# 7_segment.net
KiCad netlist of a schematic drawn in Altium Designer
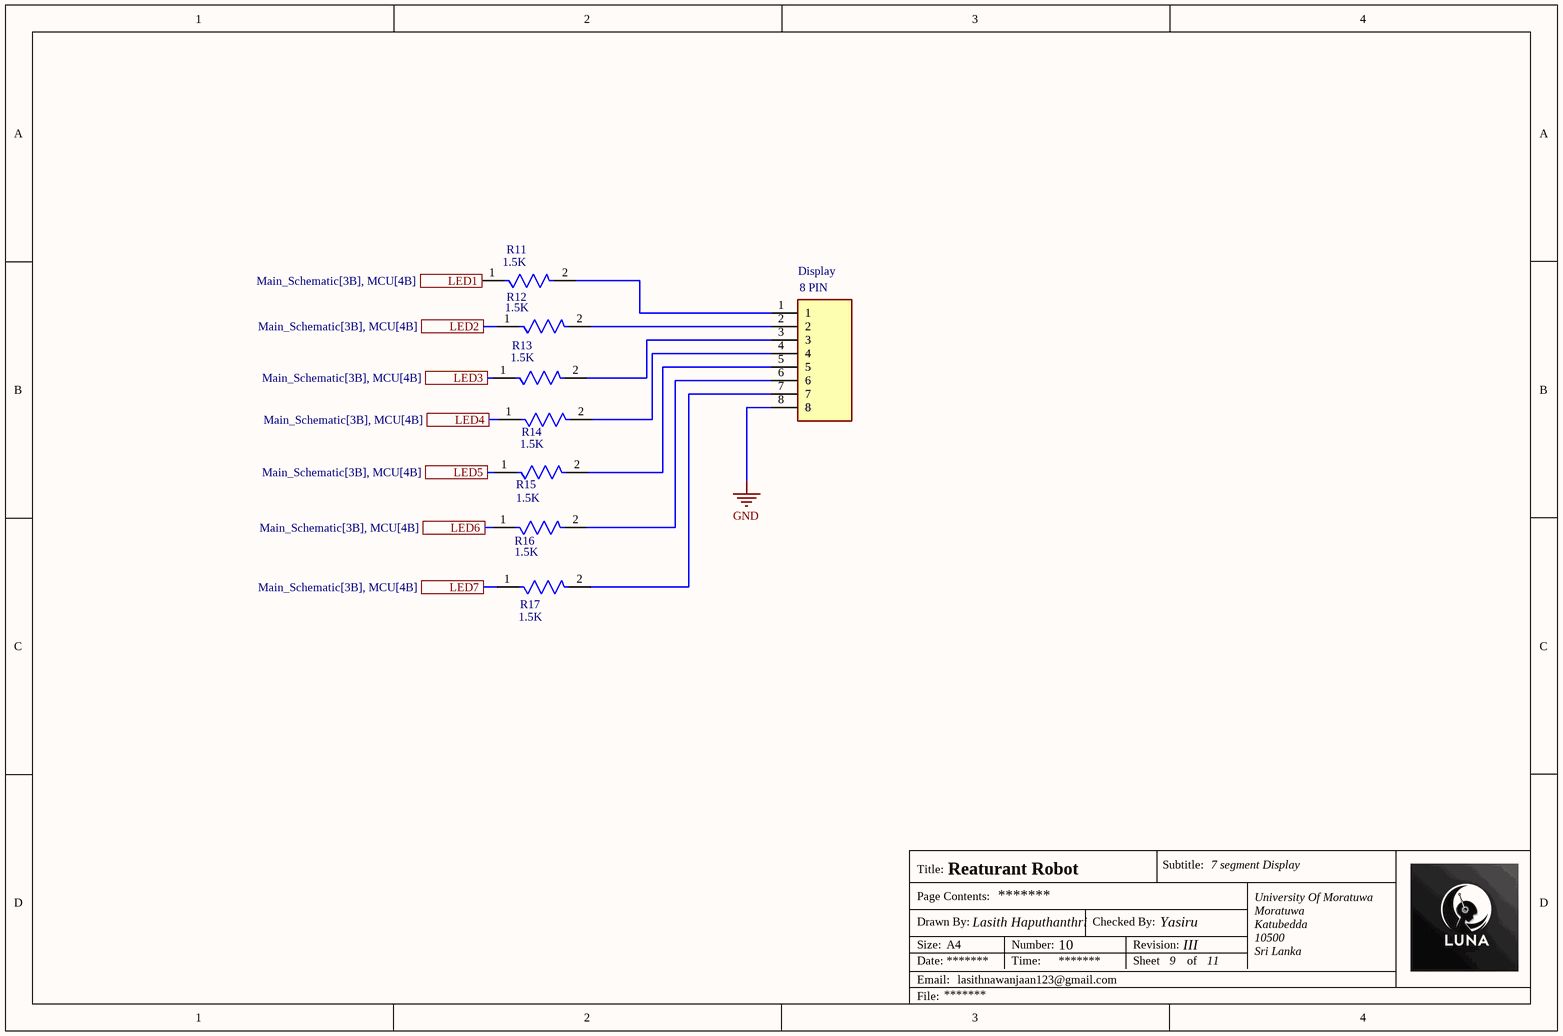
[diagram p0: 7 segment.SchDoc]

(export (version "E")
  (design (tool "Eeschema 10.0.6"))
  (components
    (comp (ref "Display")
      (value "8 PIN")
      (footprint "SamacSys:SHDR8W60P0X250_1X8_2250X640X880P")
      (description "Connector")
      (fields (field (name "MANUFACTURER_PART_NUMBER") "B08B-XASK-1 (LF)(SN)"))
      (libsource (lib "*") (part "B08B-XASK-1__LF__SN_"))
    )
    (comp (ref "R11")
      (value "1.5K")
      (footprint "FP-AF0603-IPC_B")
      (description "Anti-Sulfurated Chip Resistors Automotive Grade 1.5kΩ 1% 100ppm/°C 0603")
      (fields (field (name "TOLERANCE") "1%"))
      (libsource (lib "Altium Content Vault") (part "1029c3af85768c4190bb7ad29bc67b5"))
    )
    (comp (ref "R12")
      (value "1.5K")
      (footprint "FP-AF0603-IPC_B")
      (description "Anti-Sulfurated Chip Resistors Automotive Grade 1.5kΩ 1% 100ppm/°C 0603")
      (fields (field (name "TOLERANCE") "1%"))
      (libsource (lib "Altium Content Vault") (part "1029c3af85768c4190bb7ad29bc67b5"))
    )
    (comp (ref "R13")
      (value "1.5K")
      (footprint "FP-AF0603-IPC_B")
      (description "Anti-Sulfurated Chip Resistors Automotive Grade 1.5kΩ 1% 100ppm/°C 0603")
      (fields (field (name "TOLERANCE") "1%"))
      (libsource (lib "Altium Content Vault") (part "1029c3af85768c4190bb7ad29bc67b5"))
    )
    (comp (ref "R14")
      (value "1.5K")
      (footprint "FP-AF0603-IPC_B")
      (description "Anti-Sulfurated Chip Resistors Automotive Grade 1.5kΩ 1% 100ppm/°C 0603")
      (fields (field (name "TOLERANCE") "1%"))
      (libsource (lib "Altium Content Vault") (part "1029c3af85768c4190bb7ad29bc67b5"))
    )
    (comp (ref "R15")
      (value "1.5K")
      (footprint "FP-AF0603-IPC_B")
      (description "Anti-Sulfurated Chip Resistors Automotive Grade 1.5kΩ 1% 100ppm/°C 0603")
      (fields (field (name "TOLERANCE") "1%"))
      (libsource (lib "Altium Content Vault") (part "1029c3af85768c4190bb7ad29bc67b5"))
    )
    (comp (ref "R16")
      (value "1.5K")
      (footprint "FP-AF0603-IPC_B")
      (description "Anti-Sulfurated Chip Resistors Automotive Grade 1.5kΩ 1% 100ppm/°C 0603")
      (fields (field (name "TOLERANCE") "1%"))
      (libsource (lib "Altium Content Vault") (part "1029c3af85768c4190bb7ad29bc67b5"))
    )
    (comp (ref "R17")
      (value "1.5K")
      (footprint "FP-AF0603-IPC_B")
      (description "Anti-Sulfurated Chip Resistors Automotive Grade 1.5kΩ 1% 100ppm/°C 0603")
      (fields (field (name "TOLERANCE") "1%"))
      (libsource (lib "Altium Content Vault") (part "1029c3af85768c4190bb7ad29bc67b5"))
    )
  )
  (nets
    (net (code "1") (name "/LED1") (class "Default")
      (node (ref "R11") (pin "1") (pinfunction "1_1") (pintype "passive"))
    )
    (net (code "2") (name "/LED2") (class "Default")
      (node (ref "R12") (pin "1") (pinfunction "1_1") (pintype "passive"))
    )
    (net (code "3") (name "/LED3") (class "Default")
      (node (ref "R13") (pin "1") (pinfunction "1_1") (pintype "passive"))
    )
    (net (code "4") (name "/LED4") (class "Default")
      (node (ref "R14") (pin "1") (pinfunction "1_1") (pintype "passive"))
    )
    (net (code "5") (name "/LED5") (class "Default")
      (node (ref "R15") (pin "1") (pinfunction "1_1") (pintype "passive"))
    )
    (net (code "6") (name "/LED6") (class "Default")
      (node (ref "R16") (pin "1") (pinfunction "1_1") (pintype "passive"))
    )
    (net (code "7") (name "/LED7") (class "Default")
      (node (ref "R17") (pin "1") (pinfunction "1_1") (pintype "passive"))
    )
    (net (code "8") (name "GND") (class "Default")
      (node (ref "Display") (pin "8") (pinfunction "8_8") (pintype "passive"))
    )
    (net (code "9") (name "Net-(Display-Pad1)") (class "Default")
      (node (ref "Display") (pin "1") (pinfunction "1_1") (pintype "passive"))
      (node (ref "R11") (pin "2") (pinfunction "2_2") (pintype "passive"))
    )
    (net (code "10") (name "Net-(Display-Pad2)") (class "Default")
      (node (ref "Display") (pin "2") (pinfunction "2_2") (pintype "passive"))
      (node (ref "R12") (pin "2") (pinfunction "2_2") (pintype "passive"))
    )
    (net (code "11") (name "Net-(Display-Pad3)") (class "Default")
      (node (ref "Display") (pin "3") (pinfunction "3_3") (pintype "passive"))
      (node (ref "R13") (pin "2") (pinfunction "2_2") (pintype "passive"))
    )
    (net (code "12") (name "Net-(Display-Pad4)") (class "Default")
      (node (ref "Display") (pin "4") (pinfunction "4_4") (pintype "passive"))
      (node (ref "R14") (pin "2") (pinfunction "2_2") (pintype "passive"))
    )
    (net (code "13") (name "Net-(Display-Pad5)") (class "Default")
      (node (ref "Display") (pin "5") (pinfunction "5_5") (pintype "passive"))
      (node (ref "R15") (pin "2") (pinfunction "2_2") (pintype "passive"))
    )
    (net (code "14") (name "Net-(Display-Pad6)") (class "Default")
      (node (ref "Display") (pin "6") (pinfunction "6_6") (pintype "passive"))
      (node (ref "R16") (pin "2") (pinfunction "2_2") (pintype "passive"))
    )
    (net (code "15") (name "Net-(Display-Pad7)") (class "Default")
      (node (ref "Display") (pin "7") (pinfunction "7_7") (pintype "passive"))
      (node (ref "R17") (pin "2") (pinfunction "2_2") (pintype "passive"))
    )
  )
)
